# LPC_Rep.net
KiCad netlist of a schematic drawn in Altium Designer
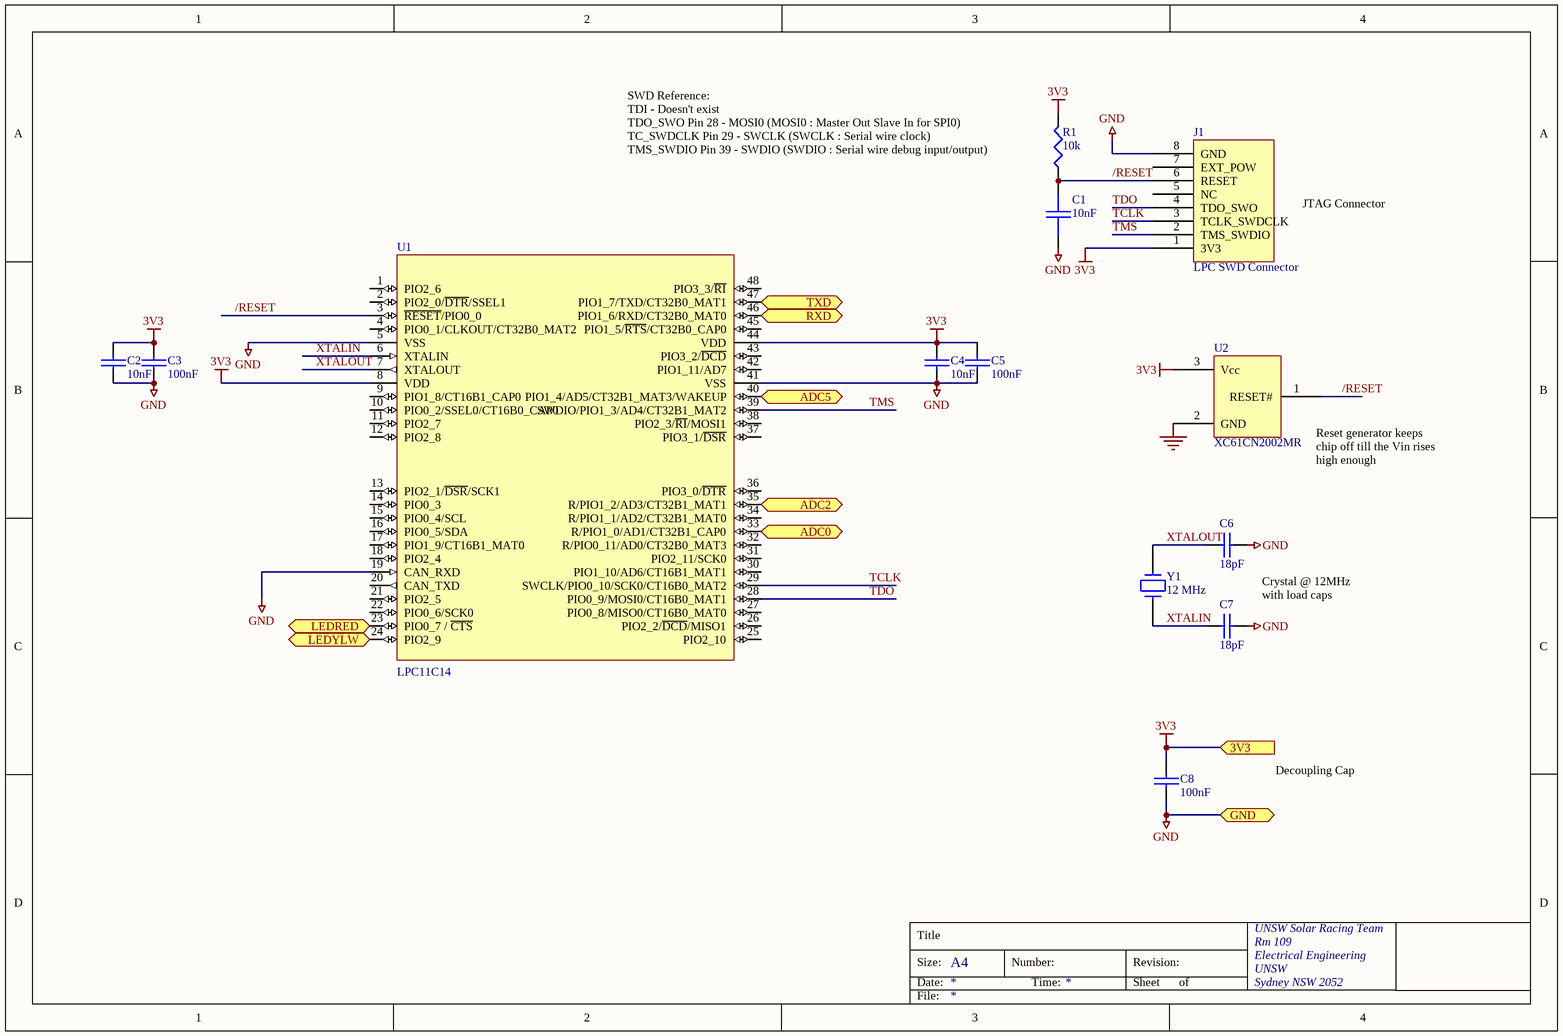
[diagram p0: LPC_Rep.SchDoc]

(export (version "E")
  (design (tool "Eeschema 10.0.6"))
  (components
    (comp (ref "C1")
      (value "10nF")
      (footprint "0603")
      (description "Capacitor")
      (libsource (lib "SunswiftLib20030312RR") (part "CAP"))
    )
    (comp (ref "C2")
      (value "10nF")
      (footprint "0603")
      (description "Capacitor")
      (libsource (lib "*") (part "CAP"))
    )
    (comp (ref "C3")
      (value "100nF")
      (footprint "0603")
      (description "Capacitor")
      (libsource (lib "*") (part "CAP"))
    )
    (comp (ref "C4")
      (value "10nF")
      (footprint "0603")
      (description "Capacitor")
      (libsource (lib "*") (part "CAP"))
    )
    (comp (ref "C5")
      (value "100nF")
      (footprint "0603")
      (description "Capacitor")
      (libsource (lib "*") (part "CAP"))
    )
    (comp (ref "C6")
      (value "18pF")
      (footprint "0603")
      (description "Capacitor")
      (libsource (lib "*") (part "CAP"))
    )
    (comp (ref "C7")
      (value "18pF")
      (footprint "0603")
      (description "Capacitor")
      (libsource (lib "*") (part "CAP"))
    )
    (comp (ref "C8")
      (value "100nF")
      (footprint "0603")
      (description "Capacitor")
      (libsource (lib "*") (part "CAP"))
    )
    (comp (ref "J1")
      (value "LPC SWD Connector")
      (footprint "Footprint:IDC8")
      (libsource (lib "2009_BatteryMaster") (part "LPCLink_Connector"))
    )
    (comp (ref "R1")
      (value "10k")
      (footprint "0603")
      (description "Resistor")
      (libsource (lib "SunswiftLib20030312RR") (part "RES1"))
    )
    (comp (ref "U1")
      (value "LPC11C14")
      (footprint "TSQFP50P900X900-48N")
      (libsource (lib "LPC") (part "LPC11C14_Full"))
    )
    (comp (ref "U2")
      (value "XC61CN2002MR")
      (footprint "SOT23-3")
      (description "SOT23 reset generator")
      (libsource (lib "*") (part "XC61F"))
    )
    (comp (ref "Y1")
      (value "12 MHz")
      (footprint "HC49/4H")
      (description "Crystal")
      (libsource (lib "*") (part "CRYSTAL"))
    )
  )
  (nets
    (net (code "1") (name "/ADC0") (class "Default")
      (node (ref "U1") (pin "33") (pinfunction "R/PIO1_0/AD1/CT32B1_CAP0_33") (pintype "bidirectional"))
    )
    (net (code "2") (name "/ADC2") (class "Default")
      (node (ref "U1") (pin "35") (pinfunction "R/PIO1_2/AD3/CT32B1_MAT1_35") (pintype "bidirectional"))
    )
    (net (code "3") (name "/ADC5") (class "Default")
      (node (ref "U1") (pin "40") (pinfunction "PIO1_4/AD5/CT32B1_MAT3/WAKEUP_40") (pintype "bidirectional"))
    )
    (net (code "4") (name "/LEDRED") (class "Default")
      (node (ref "U1") (pin "23") (pinfunction "PIO0_7_/_~{CTS}_23") (pintype "bidirectional"))
    )
    (net (code "5") (name "/LEDYLW") (class "Default")
      (node (ref "U1") (pin "24") (pinfunction "PIO2_9_24") (pintype "bidirectional"))
    )
    (net (code "6") (name "/RXD") (class "Default")
      (node (ref "U1") (pin "46") (pinfunction "PIO1_6/RXD/CT32B0_MAT0_46") (pintype "bidirectional"))
    )
    (net (code "7") (name "/TCLK") (class "Default")
      (node (ref "J1") (pin "3") (pinfunction "TCLK_SWDCLK_3") (pintype "passive"))
      (node (ref "U1") (pin "29") (pinfunction "SWCLK/PIO0_10/SCK0/CT16B0_MAT2_29") (pintype "bidirectional"))
    )
    (net (code "8") (name "/TDO") (class "Default")
      (node (ref "J1") (pin "4") (pinfunction "TDO_SWO_4") (pintype "passive"))
      (node (ref "U1") (pin "28") (pinfunction "PIO0_9/MOSI0/CT16B0_MAT1_28") (pintype "bidirectional"))
    )
    (net (code "9") (name "/TMS") (class "Default")
      (node (ref "J1") (pin "2") (pinfunction "TMS_SWDIO_2") (pintype "passive"))
      (node (ref "U1") (pin "39") (pinfunction "SWDIO/PIO1_3/AD4/CT32B1_MAT2_39") (pintype "bidirectional"))
    )
    (net (code "10") (name "/TXD") (class "Default")
      (node (ref "U1") (pin "47") (pinfunction "PIO1_7/TXD/CT32B0_MAT1_47") (pintype "bidirectional"))
    )
    (net (code "11") (name "/XTALIN") (class "Default")
      (node (ref "C7") (pin "1") (pinfunction "1_1") (pintype "passive"))
      (node (ref "U1") (pin "6") (pinfunction "XTALIN_6") (pintype "input"))
      (node (ref "Y1") (pin "1") (pinfunction "1_1") (pintype "passive"))
    )
    (net (code "12") (name "/XTALOUT") (class "Default")
      (node (ref "C6") (pin "1") (pinfunction "1_1") (pintype "passive"))
      (node (ref "U1") (pin "7") (pinfunction "XTALOUT_7") (pintype "output"))
      (node (ref "Y1") (pin "2") (pinfunction "2_2") (pintype "passive"))
    )
    (net (code "13") (name "/{slash}RESET") (class "Default")
      (node (ref "C1") (pin "1") (pinfunction "1_1") (pintype "passive"))
      (node (ref "J1") (pin "6") (pinfunction "RESET_6") (pintype "passive"))
      (node (ref "R1") (pin "1") (pinfunction "1_1") (pintype "passive"))
      (node (ref "U1") (pin "3") (pinfunction "~{RESET}/PIO0_0_3") (pintype "bidirectional"))
      (node (ref "U2") (pin "1") (pinfunction "RESET#_1") (pintype "passive"))
    )
    (net (code "14") (name "3V3") (class "Default")
      (node (ref "C2") (pin "2") (pinfunction "2_2") (pintype "passive"))
      (node (ref "C3") (pin "2") (pinfunction "2_2") (pintype "passive"))
      (node (ref "C4") (pin "2") (pinfunction "2_2") (pintype "passive"))
      (node (ref "C5") (pin "2") (pinfunction "2_2") (pintype "passive"))
      (node (ref "C8") (pin "1") (pinfunction "1_1") (pintype "passive"))
      (node (ref "J1") (pin "1") (pinfunction "3V3_1") (pintype "passive"))
      (node (ref "R1") (pin "2") (pinfunction "2_2") (pintype "passive"))
      (node (ref "U1") (pin "44") (pinfunction "VDD_44") (pintype "power_in"))
      (node (ref "U1") (pin "8") (pinfunction "VDD_8") (pintype "power_in"))
      (node (ref "U2") (pin "3") (pinfunction "Vcc_3") (pintype "passive"))
    )
    (net (code "15") (name "GND") (class "Default")
      (node (ref "C1") (pin "2") (pinfunction "2_2") (pintype "passive"))
      (node (ref "C2") (pin "1") (pinfunction "1_1") (pintype "passive"))
      (node (ref "C3") (pin "1") (pinfunction "1_1") (pintype "passive"))
      (node (ref "C4") (pin "1") (pinfunction "1_1") (pintype "passive"))
      (node (ref "C5") (pin "1") (pinfunction "1_1") (pintype "passive"))
      (node (ref "C6") (pin "2") (pinfunction "2_2") (pintype "passive"))
      (node (ref "C7") (pin "2") (pinfunction "2_2") (pintype "passive"))
      (node (ref "C8") (pin "2") (pinfunction "2_2") (pintype "passive"))
      (node (ref "J1") (pin "8") (pinfunction "GND_8") (pintype "passive"))
      (node (ref "U1") (pin "19") (pinfunction "CAN_RXD_19") (pintype "input"))
      (node (ref "U1") (pin "41") (pinfunction "VSS_41") (pintype "power_in"))
      (node (ref "U1") (pin "5") (pinfunction "VSS_5") (pintype "power_in"))
      (node (ref "U2") (pin "2") (pinfunction "GND_2") (pintype "passive"))
    )
    (net (code "16") (name "unconnected-(J1-EXT_POW-Pad7)") (class "Default")
      (node (ref "J1") (pin "7") (pinfunction "EXT_POW_7") (pintype "passive"))
    )
    (net (code "17") (name "unconnected-(J1-NC-Pad5)") (class "Default")
      (node (ref "J1") (pin "5") (pinfunction "NC_5") (pintype "passive"))
    )
    (net (code "18") (name "unconnected-(U1-CAN_TXD-Pad20)") (class "Default")
      (node (ref "U1") (pin "20") (pinfunction "CAN_TXD_20") (pintype "output"))
    )
    (net (code "19") (name "unconnected-(U1-PIO0_1{slash}CLKOUT{slash}CT32B0_MAT2-Pad4)") (class "Default")
      (node (ref "U1") (pin "4") (pinfunction "PIO0_1/CLKOUT/CT32B0_MAT2_4") (pintype "bidirectional"))
    )
    (net (code "20") (name "unconnected-(U1-PIO0_2{slash}SSEL0{slash}CT16B0_CAP0-Pad10)") (class "Default")
      (node (ref "U1") (pin "10") (pinfunction "PIO0_2/SSEL0/CT16B0_CAP0_10") (pintype "bidirectional"))
    )
    (net (code "21") (name "unconnected-(U1-PIO0_3-Pad14)") (class "Default")
      (node (ref "U1") (pin "14") (pinfunction "PIO0_3_14") (pintype "bidirectional"))
    )
    (net (code "22") (name "unconnected-(U1-PIO0_4{slash}SCL-Pad15)") (class "Default")
      (node (ref "U1") (pin "15") (pinfunction "PIO0_4/SCL_15") (pintype "bidirectional"))
    )
    (net (code "23") (name "unconnected-(U1-PIO0_5{slash}SDA-Pad16)") (class "Default")
      (node (ref "U1") (pin "16") (pinfunction "PIO0_5/SDA_16") (pintype "bidirectional"))
    )
    (net (code "24") (name "unconnected-(U1-PIO0_6{slash}SCK0-Pad22)") (class "Default")
      (node (ref "U1") (pin "22") (pinfunction "PIO0_6/SCK0_22") (pintype "bidirectional"))
    )
    (net (code "25") (name "unconnected-(U1-PIO0_8{slash}MISO0{slash}CT16B0_MAT0-Pad27)") (class "Default")
      (node (ref "U1") (pin "27") (pinfunction "PIO0_8/MISO0/CT16B0_MAT0_27") (pintype "bidirectional"))
    )
    (net (code "26") (name "unconnected-(U1-PIO1_5{slash}~{RTS}{slash}CT32B0_CAP0-Pad45)") (class "Default")
      (node (ref "U1") (pin "45") (pinfunction "PIO1_5/~{RTS}/CT32B0_CAP0_45") (pintype "bidirectional"))
    )
    (net (code "27") (name "unconnected-(U1-PIO1_8{slash}CT16B1_CAP0-Pad9)") (class "Default")
      (node (ref "U1") (pin "9") (pinfunction "PIO1_8/CT16B1_CAP0_9") (pintype "bidirectional"))
    )
    (net (code "28") (name "unconnected-(U1-PIO1_9{slash}CT16B1_MAT0-Pad17)") (class "Default")
      (node (ref "U1") (pin "17") (pinfunction "PIO1_9/CT16B1_MAT0_17") (pintype "bidirectional"))
    )
    (net (code "29") (name "unconnected-(U1-PIO1_10{slash}AD6{slash}CT16B1_MAT1-Pad30)") (class "Default")
      (node (ref "U1") (pin "30") (pinfunction "PIO1_10/AD6/CT16B1_MAT1_30") (pintype "bidirectional"))
    )
    (net (code "30") (name "unconnected-(U1-PIO1_11{slash}AD7-Pad42)") (class "Default")
      (node (ref "U1") (pin "42") (pinfunction "PIO1_11/AD7_42") (pintype "bidirectional"))
    )
    (net (code "31") (name "unconnected-(U1-PIO2_0{slash}~{DTR}{slash}SSEL1-Pad2)") (class "Default")
      (node (ref "U1") (pin "2") (pinfunction "PIO2_0/~{DTR}/SSEL1_2") (pintype "bidirectional"))
    )
    (net (code "32") (name "unconnected-(U1-PIO2_1{slash}~{DSR}{slash}SCK1-Pad13)") (class "Default")
      (node (ref "U1") (pin "13") (pinfunction "PIO2_1/~{DSR}/SCK1_13") (pintype "bidirectional"))
    )
    (net (code "33") (name "unconnected-(U1-PIO2_2{slash}~{DCD}{slash}MISO1-Pad26)") (class "Default")
      (node (ref "U1") (pin "26") (pinfunction "PIO2_2/~{DCD}/MISO1_26") (pintype "bidirectional"))
    )
    (net (code "34") (name "unconnected-(U1-PIO2_3{slash}~{RI}{slash}MOSI1-Pad38)") (class "Default")
      (node (ref "U1") (pin "38") (pinfunction "PIO2_3/~{RI}/MOSI1_38") (pintype "bidirectional"))
    )
    (net (code "35") (name "unconnected-(U1-PIO2_4-Pad18)") (class "Default")
      (node (ref "U1") (pin "18") (pinfunction "PIO2_4_18") (pintype "bidirectional"))
    )
    (net (code "36") (name "unconnected-(U1-PIO2_5-Pad21)") (class "Default")
      (node (ref "U1") (pin "21") (pinfunction "PIO2_5_21") (pintype "bidirectional"))
    )
    (net (code "37") (name "unconnected-(U1-PIO2_6-Pad1)") (class "Default")
      (node (ref "U1") (pin "1") (pinfunction "PIO2_6_1") (pintype "bidirectional"))
    )
    (net (code "38") (name "unconnected-(U1-PIO2_7-Pad11)") (class "Default")
      (node (ref "U1") (pin "11") (pinfunction "PIO2_7_11") (pintype "bidirectional"))
    )
    (net (code "39") (name "unconnected-(U1-PIO2_8-Pad12)") (class "Default")
      (node (ref "U1") (pin "12") (pinfunction "PIO2_8_12") (pintype "bidirectional"))
    )
    (net (code "40") (name "unconnected-(U1-PIO2_10-Pad25)") (class "Default")
      (node (ref "U1") (pin "25") (pinfunction "PIO2_10_25") (pintype "bidirectional"))
    )
    (net (code "41") (name "unconnected-(U1-PIO2_11{slash}SCK0-Pad31)") (class "Default")
      (node (ref "U1") (pin "31") (pinfunction "PIO2_11/SCK0_31") (pintype "bidirectional"))
    )
    (net (code "42") (name "unconnected-(U1-PIO3_0{slash}~{DTR}-Pad36)") (class "Default")
      (node (ref "U1") (pin "36") (pinfunction "PIO3_0/~{DTR}_36") (pintype "bidirectional"))
    )
    (net (code "43") (name "unconnected-(U1-PIO3_1{slash}~{DSR}-Pad37)") (class "Default")
      (node (ref "U1") (pin "37") (pinfunction "PIO3_1/~{DSR}_37") (pintype "bidirectional"))
    )
    (net (code "44") (name "unconnected-(U1-PIO3_2{slash}~{DCD}-Pad43)") (class "Default")
      (node (ref "U1") (pin "43") (pinfunction "PIO3_2/~{DCD}_43") (pintype "bidirectional"))
    )
    (net (code "45") (name "unconnected-(U1-PIO3_3{slash}~{RI}-Pad48)") (class "Default")
      (node (ref "U1") (pin "48") (pinfunction "PIO3_3/~{RI}_48") (pintype "bidirectional"))
    )
    (net (code "46") (name "unconnected-(U1-R{slash}PIO0_11{slash}AD0{slash}CT32B0_MAT3-Pad32)") (class "Default")
      (node (ref "U1") (pin "32") (pinfunction "R/PIO0_11/AD0/CT32B0_MAT3_32") (pintype "bidirectional"))
    )
    (net (code "47") (name "unconnected-(U1-R{slash}PIO1_1{slash}AD2{slash}CT32B1_MAT0-Pad34)") (class "Default")
      (node (ref "U1") (pin "34") (pinfunction "R/PIO1_1/AD2/CT32B1_MAT0_34") (pintype "bidirectional"))
    )
  )
)
